# MIXR_Processing_-_STM32_DSP_Misc.net
KiCad netlist of a schematic drawn in Altium Designer
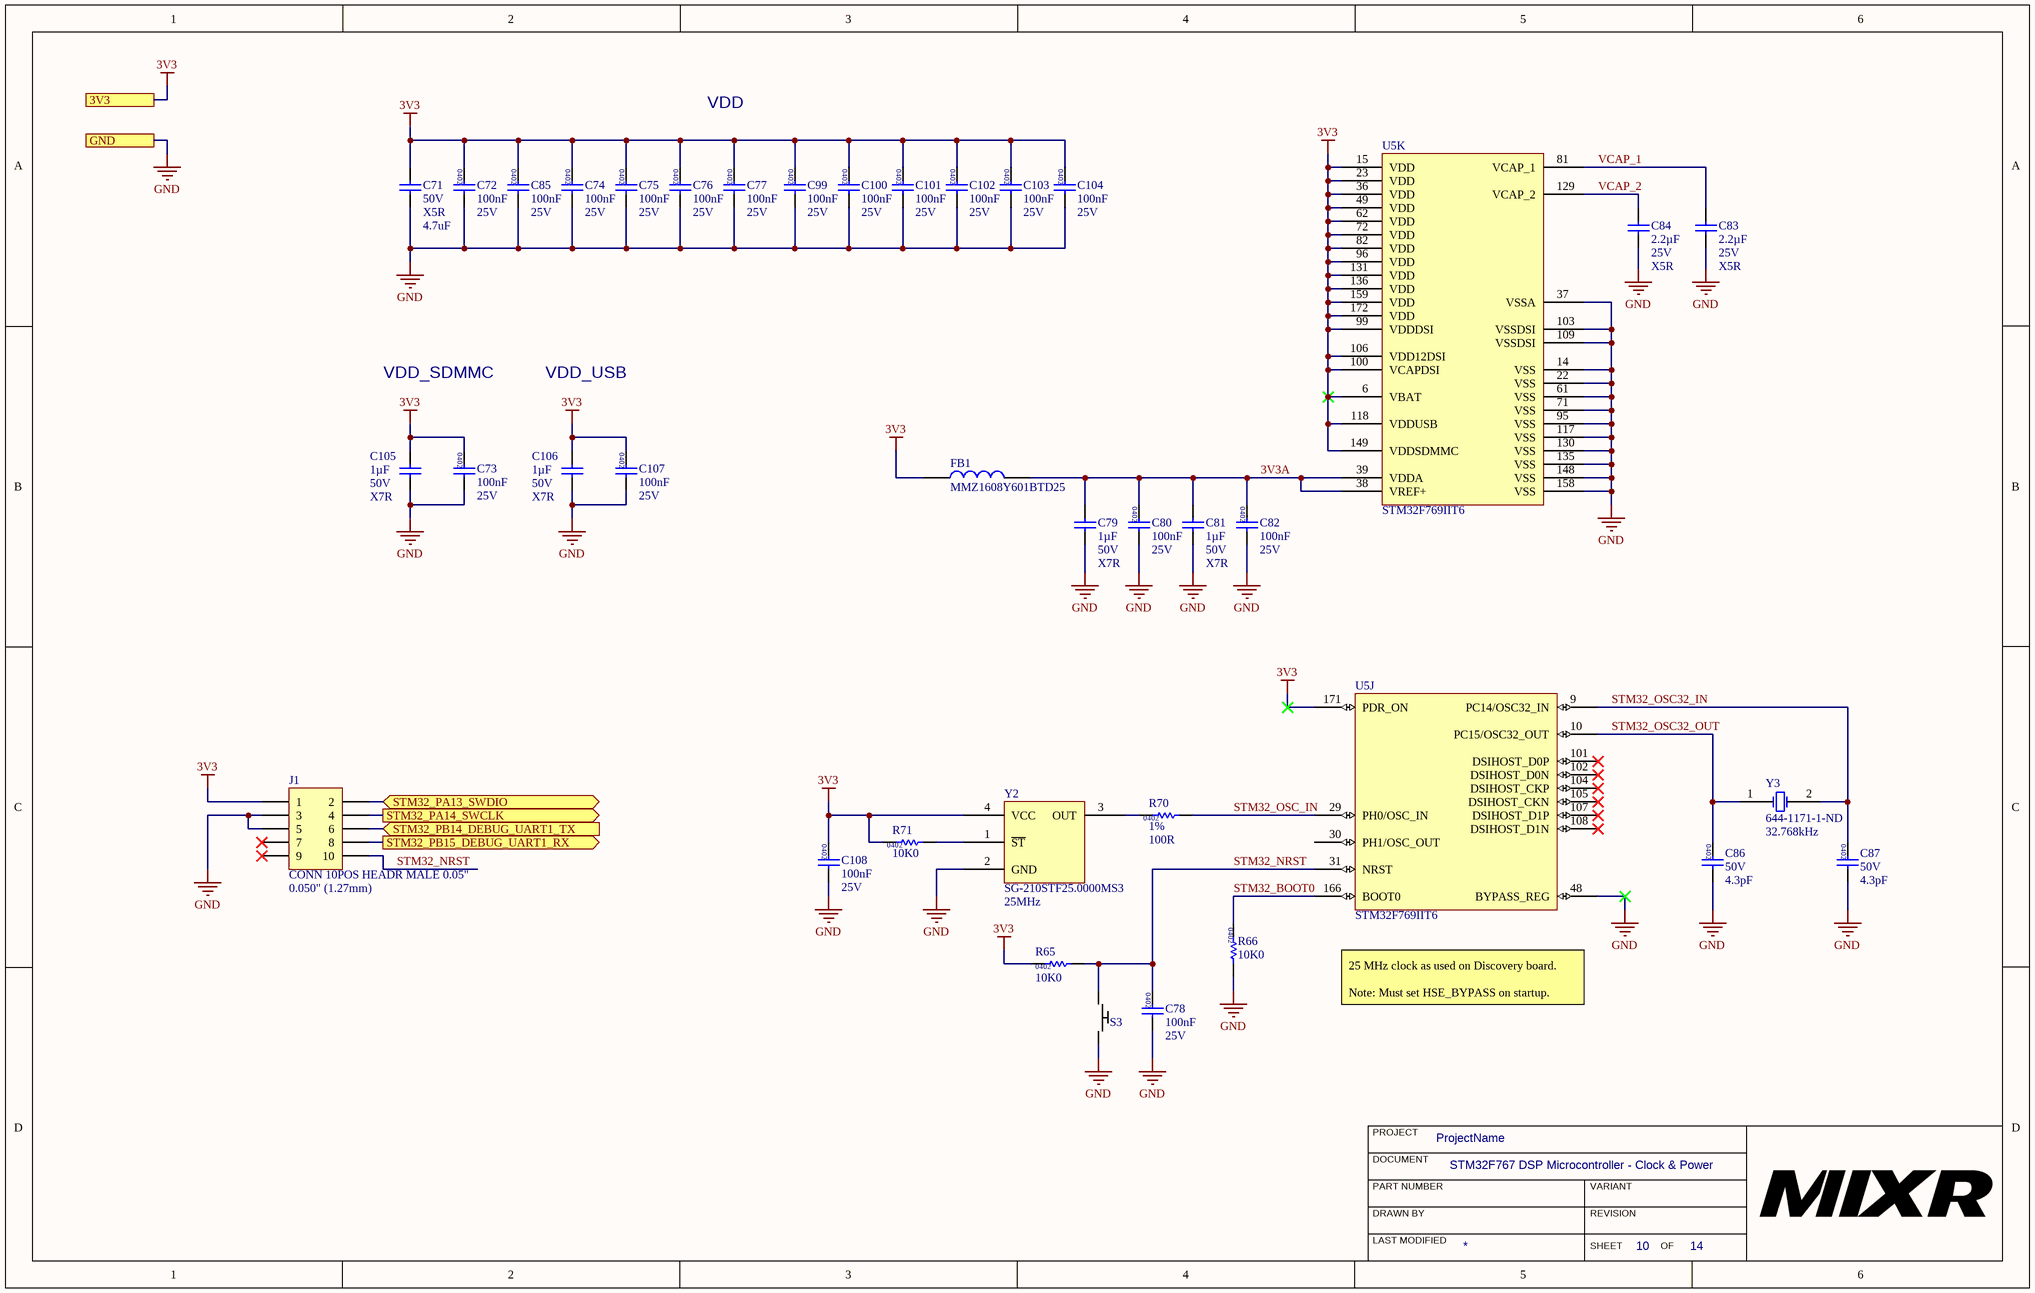
[diagram p0: MIXR Processing - STM32 DSP Misc.SchDoc]

(export (version "E")
  (design (tool "Eeschema 10.0.6"))
  (components
    (comp (ref "C71")
      (value "4.7uF")
      (footprint "CAP, 0805")
      (description "4.7µF ±20% 50V Ceramic Capacitor X5R 0805 (2012 Metric)")
      (fields
        (field (name "TOLERANCE") "±20%")
        (field (name "VOLTAGE - RATED") "50V")
        (field (name "TEMPERATURE COEFFICIENT") "X5R")
        (field (name "Comment") "CAP CER 4.7UF 50V 10% X5R 0805")
      )
      (libsource (lib "Schematic Diagrams") (part "CAP CER 4.7UF 50V 10% X5R 0805"))
    )
    (comp (ref "C72")
      (value "CAP CER 0.1UF 16V X7R 0402")
      (footprint "CAP 0402")
      (description "Cap Ceramic 0.1uF 25V X7R 10% SMD 0402 125C Paper T/R")
      (fields
        (field (name "TOLERANCE") "10%")
        (field (name "CAPACITANCE") "100nF")
        (field (name "VOLTAGE") "25V")
        (field (name "MANUFACTURER") "Murata")
      )
      (libsource (lib "Schematic Diagrams") (part "CAP CER 0.1UF 16V X7R 0402"))
    )
    (comp (ref "C73")
      (value "CAP CER 0.1UF 16V X7R 0402")
      (footprint "CAP 0402")
      (description "Cap Ceramic 0.1uF 25V X7R 10% SMD 0402 125C Paper T/R")
      (fields
        (field (name "TOLERANCE") "10%")
        (field (name "CAPACITANCE") "100nF")
        (field (name "VOLTAGE") "25V")
        (field (name "MANUFACTURER") "Murata")
      )
      (libsource (lib "Schematic Diagrams") (part "CAP CER 0.1UF 16V X7R 0402"))
    )
    (comp (ref "C74")
      (value "CAP CER 0.1UF 16V X7R 0402")
      (footprint "CAP 0402")
      (description "Cap Ceramic 0.1uF 25V X7R 10% SMD 0402 125C Paper T/R")
      (fields
        (field (name "TOLERANCE") "10%")
        (field (name "CAPACITANCE") "100nF")
        (field (name "VOLTAGE") "25V")
        (field (name "MANUFACTURER") "Murata")
      )
      (libsource (lib "Schematic Diagrams") (part "CAP CER 0.1UF 16V X7R 0402"))
    )
    (comp (ref "C75")
      (value "CAP CER 0.1UF 16V X7R 0402")
      (footprint "CAP 0402")
      (description "Cap Ceramic 0.1uF 25V X7R 10% SMD 0402 125C Paper T/R")
      (fields
        (field (name "TOLERANCE") "10%")
        (field (name "CAPACITANCE") "100nF")
        (field (name "VOLTAGE") "25V")
        (field (name "MANUFACTURER") "Murata")
      )
      (libsource (lib "Schematic Diagrams") (part "CAP CER 0.1UF 16V X7R 0402"))
    )
    (comp (ref "C76")
      (value "CAP CER 0.1UF 16V X7R 0402")
      (footprint "CAP 0402")
      (description "Cap Ceramic 0.1uF 25V X7R 10% SMD 0402 125C Paper T/R")
      (fields
        (field (name "TOLERANCE") "10%")
        (field (name "CAPACITANCE") "100nF")
        (field (name "VOLTAGE") "25V")
        (field (name "MANUFACTURER") "Murata")
      )
      (libsource (lib "Schematic Diagrams") (part "CAP CER 0.1UF 16V X7R 0402"))
    )
    (comp (ref "C77")
      (value "CAP CER 0.1UF 16V X7R 0402")
      (footprint "CAP 0402")
      (description "Cap Ceramic 0.1uF 25V X7R 10% SMD 0402 125C Paper T/R")
      (fields
        (field (name "TOLERANCE") "10%")
        (field (name "CAPACITANCE") "100nF")
        (field (name "VOLTAGE") "25V")
        (field (name "MANUFACTURER") "Murata")
      )
      (libsource (lib "Schematic Diagrams") (part "CAP CER 0.1UF 16V X7R 0402"))
    )
    (comp (ref "C78")
      (value "CAP CER 0.1UF 16V X7R 0402")
      (footprint "CAP 0402")
      (description "Cap Ceramic 0.1uF 25V X7R 10% SMD 0402 125C Paper T/R")
      (fields
        (field (name "TOLERANCE") "10%")
        (field (name "CAPACITANCE") "100nF")
        (field (name "VOLTAGE") "25V")
        (field (name "MANUFACTURER") "Murata")
      )
      (libsource (lib "Schematic Diagrams") (part "CAP CER 0.1UF 16V X7R 0402"))
    )
    (comp (ref "C79")
      (value "CAP CER 1UF 50V 10% X7R 0603")
      (footprint "CAP, 0603")
      (description "1µF ±10% 50V Ceramic Capacitor X7R 0603 (1608 Metric)")
      (fields
        (field (name "TOLERANCE") "±10%")
        (field (name "CAPACITANCE") "1µF")
        (field (name "VOLTAGE") "50V")
        (field (name "TEMPERATURE COEFFICIENT") "X7R")
      )
      (libsource (lib "Schematic Diagrams") (part "CAP CER 1UF 50V 10% X7R 0603"))
    )
    (comp (ref "C80")
      (value "CAP CER 0.1UF 16V X7R 0402")
      (footprint "CAP 0402")
      (description "Cap Ceramic 0.1uF 25V X7R 10% SMD 0402 125C Paper T/R")
      (fields
        (field (name "TOLERANCE") "10%")
        (field (name "CAPACITANCE") "100nF")
        (field (name "VOLTAGE") "25V")
        (field (name "MANUFACTURER") "Murata")
      )
      (libsource (lib "Schematic Diagrams") (part "CAP CER 0.1UF 16V X7R 0402"))
    )
    (comp (ref "C81")
      (value "CAP CER 1UF 50V 10% X7R 0603")
      (footprint "CAP, 0603")
      (description "1µF ±10% 50V Ceramic Capacitor X7R 0603 (1608 Metric)")
      (fields
        (field (name "TOLERANCE") "±10%")
        (field (name "CAPACITANCE") "1µF")
        (field (name "VOLTAGE") "50V")
        (field (name "TEMPERATURE COEFFICIENT") "X7R")
      )
      (libsource (lib "Schematic Diagrams") (part "CAP CER 1UF 50V 10% X7R 0603"))
    )
    (comp (ref "C82")
      (value "CAP CER 0.1UF 16V X7R 0402")
      (footprint "CAP 0402")
      (description "Cap Ceramic 0.1uF 25V X7R 10% SMD 0402 125C Paper T/R")
      (fields
        (field (name "TOLERANCE") "10%")
        (field (name "CAPACITANCE") "100nF")
        (field (name "VOLTAGE") "25V")
        (field (name "MANUFACTURER") "Murata")
      )
      (libsource (lib "Schematic Diagrams") (part "CAP CER 0.1UF 16V X7R 0402"))
    )
    (comp (ref "C83")
      (value "CAP CER 2.2UF 25V 10% X5R 0603")
      (footprint "CAP, 0603")
      (description "2.2µF ±10% 25V Ceramic Capacitor X5R 0603 (1608 Metric)")
      (fields
        (field (name "TOLERANCE") "±10%")
        (field (name "CAPACITANCE") "2.2µF")
        (field (name "VOLTAGE") "25V")
        (field (name "TEMPERATURE COEFFICIENT") "X5R")
      )
      (libsource (lib "Schematic Diagrams") (part "CAP CER 2.2UF 25V 10% X5R 0603"))
    )
    (comp (ref "C84")
      (value "CAP CER 2.2UF 25V 10% X5R 0603")
      (footprint "CAP, 0603")
      (description "2.2µF ±10% 25V Ceramic Capacitor X5R 0603 (1608 Metric)")
      (fields
        (field (name "TOLERANCE") "±10%")
        (field (name "CAPACITANCE") "2.2µF")
        (field (name "VOLTAGE") "25V")
        (field (name "TEMPERATURE COEFFICIENT") "X5R")
      )
      (libsource (lib "Schematic Diagrams") (part "CAP CER 2.2UF 25V 10% X5R 0603"))
    )
    (comp (ref "C85")
      (value "CAP CER 0.1UF 16V X7R 0402")
      (footprint "CAP 0402")
      (description "Cap Ceramic 0.1uF 25V X7R 10% SMD 0402 125C Paper T/R")
      (fields
        (field (name "TOLERANCE") "10%")
        (field (name "CAPACITANCE") "100nF")
        (field (name "VOLTAGE") "25V")
        (field (name "MANUFACTURER") "Murata")
      )
      (libsource (lib "Schematic Diagrams") (part "CAP CER 0.1UF 16V X7R 0402"))
    )
    (comp (ref "C86")
      (value "CAP CER 4.3PF 50V C0G/NPO 0402")
      (footprint "CAP 0402")
      (description "Multilayer Ceramic Capacitors MLCC - SMD/SMT 0402 4.3pF 50Volts C0G +/-0.1pF")
      (fields
        (field (name "MANUFACTURER") "Murata")
        (field (name "MANUFACTURER PART NUMBER") "GJM1555C1H4R3BB01D")
        (field (name "VOLTAGE RATING") "50V")
        (field (name "CAPACITANCE") "4.3pF")
      )
      (libsource (lib "Schematic Diagrams") (part "CAP CER 4.3PF 50V C0G/NPO 0402"))
    )
    (comp (ref "C87")
      (value "CAP CER 4.3PF 50V C0G/NPO 0402")
      (footprint "CAP 0402")
      (description "Multilayer Ceramic Capacitors MLCC - SMD/SMT 0402 4.3pF 50Volts C0G +/-0.1pF")
      (fields
        (field (name "MANUFACTURER") "Murata")
        (field (name "MANUFACTURER PART NUMBER") "GJM1555C1H4R3BB01D")
        (field (name "VOLTAGE RATING") "50V")
        (field (name "CAPACITANCE") "4.3pF")
      )
      (libsource (lib "Schematic Diagrams") (part "CAP CER 4.3PF 50V C0G/NPO 0402"))
    )
    (comp (ref "C99")
      (value "CAP CER 0.1UF 16V X7R 0402")
      (footprint "CAP 0402")
      (description "Cap Ceramic 0.1uF 25V X7R 10% SMD 0402 125C Paper T/R")
      (fields
        (field (name "TOLERANCE") "10%")
        (field (name "CAPACITANCE") "100nF")
        (field (name "VOLTAGE") "25V")
        (field (name "MANUFACTURER") "Murata")
      )
      (libsource (lib "Schematic Diagrams") (part "CAP CER 0.1UF 16V X7R 0402"))
    )
    (comp (ref "C100")
      (value "CAP CER 0.1UF 16V X7R 0402")
      (footprint "CAP 0402")
      (description "Cap Ceramic 0.1uF 25V X7R 10% SMD 0402 125C Paper T/R")
      (fields
        (field (name "TOLERANCE") "10%")
        (field (name "CAPACITANCE") "100nF")
        (field (name "VOLTAGE") "25V")
        (field (name "MANUFACTURER") "Murata")
      )
      (libsource (lib "Schematic Diagrams") (part "CAP CER 0.1UF 16V X7R 0402"))
    )
    (comp (ref "C101")
      (value "CAP CER 0.1UF 16V X7R 0402")
      (footprint "CAP 0402")
      (description "Cap Ceramic 0.1uF 25V X7R 10% SMD 0402 125C Paper T/R")
      (fields
        (field (name "TOLERANCE") "10%")
        (field (name "CAPACITANCE") "100nF")
        (field (name "VOLTAGE") "25V")
        (field (name "MANUFACTURER") "Murata")
      )
      (libsource (lib "Schematic Diagrams") (part "CAP CER 0.1UF 16V X7R 0402"))
    )
    (comp (ref "C102")
      (value "CAP CER 0.1UF 16V X7R 0402")
      (footprint "CAP 0402")
      (description "Cap Ceramic 0.1uF 25V X7R 10% SMD 0402 125C Paper T/R")
      (fields
        (field (name "TOLERANCE") "10%")
        (field (name "CAPACITANCE") "100nF")
        (field (name "VOLTAGE") "25V")
        (field (name "MANUFACTURER") "Murata")
      )
      (libsource (lib "Schematic Diagrams") (part "CAP CER 0.1UF 16V X7R 0402"))
    )
    (comp (ref "C103")
      (value "CAP CER 0.1UF 16V X7R 0402")
      (footprint "CAP 0402")
      (description "Cap Ceramic 0.1uF 25V X7R 10% SMD 0402 125C Paper T/R")
      (fields
        (field (name "TOLERANCE") "10%")
        (field (name "CAPACITANCE") "100nF")
        (field (name "VOLTAGE") "25V")
        (field (name "MANUFACTURER") "Murata")
      )
      (libsource (lib "Schematic Diagrams") (part "CAP CER 0.1UF 16V X7R 0402"))
    )
    (comp (ref "C104")
      (value "CAP CER 0.1UF 16V X7R 0402")
      (footprint "CAP 0402")
      (description "Cap Ceramic 0.1uF 25V X7R 10% SMD 0402 125C Paper T/R")
      (fields
        (field (name "TOLERANCE") "10%")
        (field (name "CAPACITANCE") "100nF")
        (field (name "VOLTAGE") "25V")
        (field (name "MANUFACTURER") "Murata")
      )
      (libsource (lib "Schematic Diagrams") (part "CAP CER 0.1UF 16V X7R 0402"))
    )
    (comp (ref "C105")
      (value "CAP CER 1UF 50V 10% X7R 0603")
      (footprint "CAP, 0603")
      (description "1µF ±10% 50V Ceramic Capacitor X7R 0603 (1608 Metric)")
      (fields
        (field (name "TOLERANCE") "±10%")
        (field (name "CAPACITANCE") "1µF")
        (field (name "VOLTAGE") "50V")
        (field (name "TEMPERATURE COEFFICIENT") "X7R")
      )
      (libsource (lib "Schematic Diagrams") (part "CAP CER 1UF 50V 10% X7R 0603"))
    )
    (comp (ref "C106")
      (value "CAP CER 1UF 50V 10% X7R 0603")
      (footprint "CAP, 0603")
      (description "1µF ±10% 50V Ceramic Capacitor X7R 0603 (1608 Metric)")
      (fields
        (field (name "TOLERANCE") "±10%")
        (field (name "CAPACITANCE") "1µF")
        (field (name "VOLTAGE") "50V")
        (field (name "TEMPERATURE COEFFICIENT") "X7R")
      )
      (libsource (lib "Schematic Diagrams") (part "CAP CER 1UF 50V 10% X7R 0603"))
    )
    (comp (ref "C107")
      (value "CAP CER 0.1UF 16V X7R 0402")
      (footprint "CAP 0402")
      (description "Cap Ceramic 0.1uF 25V X7R 10% SMD 0402 125C Paper T/R")
      (fields
        (field (name "TOLERANCE") "10%")
        (field (name "CAPACITANCE") "100nF")
        (field (name "VOLTAGE") "25V")
        (field (name "MANUFACTURER") "Murata")
      )
      (libsource (lib "Schematic Diagrams") (part "CAP CER 0.1UF 16V X7R 0402"))
    )
    (comp (ref "C108")
      (value "CAP CER 0.1UF 16V X7R 0402")
      (footprint "CAP 0402")
      (description "Cap Ceramic 0.1uF 25V X7R 10% SMD 0402 125C Paper T/R")
      (fields
        (field (name "TOLERANCE") "10%")
        (field (name "CAPACITANCE") "100nF")
        (field (name "VOLTAGE") "25V")
        (field (name "MANUFACTURER") "Murata")
      )
      (libsource (lib "Schematic Diagrams") (part "CAP CER 0.1UF 16V X7R 0402"))
    )
    (comp (ref "FB1")
      (value "FB 600 OHM 1LN 0603")
      (footprint "FB 0603")
      (description "FERRITE BEAD 600 OHM 0603 1LN")
      (fields
        (field (name "MANUFACTURER") "TDK")
        (field (name "TOLERANCE") "25%")
        (field (name "MANUFACTURER PART NUMBER") "MMZ1608Y601BTD25")
      )
      (libsource (lib "Schematic Diagrams") (part "FB 600 OHM 1LN 0603"))
    )
    (comp (ref "J1")
      (value "CONN 10POS HEADR MALE 0.05\"")
      (footprint "CONN, 10POS 0.05\" Debug Header")
      (description "10 Positions Header Connector 0.050\" (1.27mm) Surface Mount Gold")
      (fields (field (name "PITCH - MATING") "0.050\" (1.27mm)"))
      (libsource (lib "Schematic Diagrams") (part "CONN 10POS HEADR MALE 0.05{dblquote}"))
    )
    (comp (ref "R65")
      (value "RES 10K OHM 1% 1/16W 0402")
      (footprint "RES 0402")
      (description "Surface Mount Thick Film Resistor, Rc Series, 10 Kohm, 62.5 Mw, - 1%, 50 V, 0402 [1005 Metric]")
      (fields
        (field (name "TOLERANCE") "1%")
        (field (name "RESISTANCE") "10K0")
        (field (name "MANUFACTURER") "Yageo")
      )
      (libsource (lib "Schematic Diagrams") (part "RES 10K OHM 1% 1/16W 0402"))
    )
    (comp (ref "R66")
      (value "RES 10K OHM 1% 1/16W 0402")
      (footprint "RES 0402")
      (description "Surface Mount Thick Film Resistor, Rc Series, 10 Kohm, 62.5 Mw, - 1%, 50 V, 0402 [1005 Metric]")
      (fields
        (field (name "TOLERANCE") "1%")
        (field (name "RESISTANCE") "10K0")
        (field (name "MANUFACTURER") "Yageo")
      )
      (libsource (lib "Schematic Diagrams") (part "RES 10K OHM 1% 1/16W 0402"))
    )
    (comp (ref "R70")
      (value "RES 100 OHM 1% 1/16W 0402")
      (footprint "RES 0402")
      (description "100 Ohms ±1% 0.063W, 1/16W Chip Resistor 0402 (1005 Metric) Moisture Resistant Thick Film")
      (fields
        (field (name "MANUFACTURER") "Yageo")
        (field (name "MANUFACTURER PART NUMBER") "RC0402FR-07100RL")
        (field (name "TOLERANCE") "1%")
        (field (name "RESISTANCE") "100R")
      )
      (libsource (lib "Schematic Diagrams") (part "RES 100 OHM 1% 1/16W 0402"))
    )
    (comp (ref "R71")
      (value "RES 10K OHM 1% 1/16W 0402")
      (footprint "RES 0402")
      (description "Surface Mount Thick Film Resistor, Rc Series, 10 Kohm, 62.5 Mw, - 1%, 50 V, 0402 [1005 Metric]")
      (fields
        (field (name "TOLERANCE") "1%")
        (field (name "RESISTANCE") "10K0")
        (field (name "MANUFACTURER") "Yageo")
      )
      (libsource (lib "Schematic Diagrams") (part "RES 10K OHM 1% 1/16W 0402"))
    )
    (comp (ref "S3")
      (value "SPST")
      (footprint "SW SPST-NO 0.05A 12V")
      (description "SWITCH TACTILE SPST-NO 50MA 12V")
      (fields
        (field (name "MANUFACTURER") "E-Switch")
        (field (name "MANUFACTURER PART NUMBER") "TL3305AF260QG")
      )
      (libsource (lib "Schematic Diagrams") (part "SW SPST-NO 0.05A 12V"))
    )
    (comp (ref "U5")
      (value "IC MCU STM32F769II 176-LQFP")
      (footprint "TSQFP50P2600X2600X160-176M")
      (description "ARM® Cortex®-M7 STM32F7 Microcontroller IC 32-Bit 216MHz 2MB (2M x 8) FLASH 176-LQFP (24x24)")
      (fields
        (field (name "MANUFACTURER") "STMicroelectronics")
        (field (name "MANUFACTURER PART NUMBER") "STM32F769IIT6")
      )
      (libsource (lib "Schematic Diagrams") (part "IC MCU STM32F769II 176-LQFP"))
    )
    (comp (ref "Y2")
      (value "CRYSTAL 25 MHz OSC XO CMOS SMD")
      (footprint "CRYSTAL 25 MHz OSC XO CMOS SMD")
      (description "XTAL OSC XO 25.0000MHZ CMOS SMD")
      (fields
        (field (name "MANUFACTURER") "Epson")
        (field (name "MANUFACTURER PART NUMBER") "SG-210STF25.0000MS3")
        (field (name "FREQUENCY") "25MHz")
      )
      (libsource (lib "Schematic Diagrams") (part "CRYSTAL 25 MHz OSC XO CMOS SMD"))
    )
    (comp (ref "Y3")
      (value "CRYSTAL 32.7680 KHZ 6PF 2-SMD")
      (footprint "CRYSTAL 32.7680 KHZ 6PF 2-SMD")
      (description "Crystal 32.7680KHZ 6PF SMD")
      (fields
        (field (name "MANUFACTURER") "NDK")
        (field (name "MANUFACTURER PART NUMBER") "NX3215SA-32.768K-STD-MUA-14")
        (field (name "SUPPLIER PART NUMBER 1") "644-1171-1-ND")
        (field (name "FREQUENCY") "32.768kHz")
      )
      (libsource (lib "Schematic Diagrams") (part "CRYSTAL 32.7680 KHZ 6PF 2-SMD"))
    )
  )
  (nets
    (net (code "1") (name "/3V3A") (class "Default")
      (node (ref "C79") (pin "1") (pinfunction "1_1") (pintype "passive"))
      (node (ref "C80") (pin "1") (pinfunction "1_1") (pintype "passive"))
      (node (ref "C81") (pin "1") (pinfunction "1_1") (pintype "passive"))
      (node (ref "C82") (pin "1") (pinfunction "1_1") (pintype "passive"))
      (node (ref "FB1") (pin "2") (pinfunction "2_2") (pintype "passive"))
      (node (ref "U5") (pin "38") (pinfunction "VREF+_38") (pintype "power_in"))
      (node (ref "U5") (pin "39") (pinfunction "VDDA_39") (pintype "power_in"))
    )
    (net (code "2") (name "/STM32_BOOT0") (class "Default")
      (node (ref "R66") (pin "1") (pinfunction "1_1") (pintype "passive"))
      (node (ref "U5") (pin "166") (pinfunction "BOOT0_166") (pintype "bidirectional"))
    )
    (net (code "3") (name "/STM32_NRST") (class "Default")
      (node (ref "C78") (pin "1") (pinfunction "1_1") (pintype "passive"))
      (node (ref "J1") (pin "10") (pinfunction "10_10") (pintype "passive"))
      (node (ref "R65") (pin "2") (pinfunction "2_2") (pintype "passive"))
      (node (ref "S3") (pin "1") (pinfunction "1_1") (pintype "passive"))
      (node (ref "U5") (pin "31") (pinfunction "NRST_31") (pintype "bidirectional"))
    )
    (net (code "4") (name "/STM32_OSC32_IN") (class "Default")
      (node (ref "C87") (pin "1") (pinfunction "1_1") (pintype "passive"))
      (node (ref "U5") (pin "9") (pinfunction "PC14/OSC32_IN_9") (pintype "bidirectional"))
      (node (ref "Y3") (pin "2") (pinfunction "2_2") (pintype "passive"))
    )
    (net (code "5") (name "/STM32_OSC32_OUT") (class "Default")
      (node (ref "C86") (pin "1") (pinfunction "1_1") (pintype "passive"))
      (node (ref "U5") (pin "10") (pinfunction "PC15/OSC32_OUT_10") (pintype "bidirectional"))
      (node (ref "Y3") (pin "1") (pinfunction "1_1") (pintype "passive"))
    )
    (net (code "6") (name "/STM32_OSC_IN") (class "Default")
      (node (ref "R70") (pin "2") (pinfunction "2_2") (pintype "passive"))
      (node (ref "U5") (pin "29") (pinfunction "PH0/OSC_IN_29") (pintype "bidirectional"))
    )
    (net (code "7") (name "/STM32_PA13_SWDIO") (class "Default")
      (node (ref "J1") (pin "2") (pinfunction "2_2") (pintype "passive"))
    )
    (net (code "8") (name "/STM32_PA14_SWCLK") (class "Default")
      (node (ref "J1") (pin "4") (pinfunction "4_4") (pintype "passive"))
    )
    (net (code "9") (name "/STM32_PB14_DEBUG_UART1_TX") (class "Default")
      (node (ref "J1") (pin "6") (pinfunction "6_6") (pintype "passive"))
    )
    (net (code "10") (name "/STM32_PB15_DEBUG_UART1_RX") (class "Default")
      (node (ref "J1") (pin "8") (pinfunction "8_8") (pintype "passive"))
    )
    (net (code "11") (name "/VCAP_1") (class "Default")
      (node (ref "C83") (pin "1") (pinfunction "1_1") (pintype "passive"))
      (node (ref "U5") (pin "81") (pinfunction "VCAP_1_81") (pintype "power_in"))
    )
    (net (code "12") (name "/VCAP_2") (class "Default")
      (node (ref "C84") (pin "1") (pinfunction "1_1") (pintype "passive"))
      (node (ref "U5") (pin "129") (pinfunction "VCAP_2_129") (pintype "power_in"))
    )
    (net (code "13") (name "3V3") (class "Default")
      (node (ref "C100") (pin "1") (pinfunction "1_1") (pintype "passive"))
      (node (ref "C101") (pin "1") (pinfunction "1_1") (pintype "passive"))
      (node (ref "C102") (pin "1") (pinfunction "1_1") (pintype "passive"))
      (node (ref "C103") (pin "1") (pinfunction "1_1") (pintype "passive"))
      (node (ref "C104") (pin "1") (pinfunction "1_1") (pintype "passive"))
      (node (ref "C105") (pin "1") (pinfunction "1_1") (pintype "passive"))
      (node (ref "C106") (pin "1") (pinfunction "1_1") (pintype "passive"))
      (node (ref "C107") (pin "1") (pinfunction "1_1") (pintype "passive"))
      (node (ref "C108") (pin "1") (pinfunction "1_1") (pintype "passive"))
      (node (ref "C71") (pin "1") (pinfunction "1_1") (pintype "passive"))
      (node (ref "C72") (pin "1") (pinfunction "1_1") (pintype "passive"))
      (node (ref "C73") (pin "1") (pinfunction "1_1") (pintype "passive"))
      (node (ref "C74") (pin "1") (pinfunction "1_1") (pintype "passive"))
      (node (ref "C75") (pin "1") (pinfunction "1_1") (pintype "passive"))
      (node (ref "C76") (pin "1") (pinfunction "1_1") (pintype "passive"))
      (node (ref "C77") (pin "1") (pinfunction "1_1") (pintype "passive"))
      (node (ref "C85") (pin "1") (pinfunction "1_1") (pintype "passive"))
      (node (ref "C99") (pin "1") (pinfunction "1_1") (pintype "passive"))
      (node (ref "FB1") (pin "1") (pinfunction "1_1") (pintype "passive"))
      (node (ref "J1") (pin "1") (pinfunction "1_1") (pintype "passive"))
      (node (ref "R65") (pin "1") (pinfunction "1_1") (pintype "passive"))
      (node (ref "R71") (pin "1") (pinfunction "1_1") (pintype "passive"))
      (node (ref "U5") (pin "100") (pinfunction "VCAPDSI_100") (pintype "power_in"))
      (node (ref "U5") (pin "106") (pinfunction "VDD12DSI_106") (pintype "power_in"))
      (node (ref "U5") (pin "118") (pinfunction "VDDUSB_118") (pintype "power_in"))
      (node (ref "U5") (pin "131") (pinfunction "VDD_131") (pintype "power_in"))
      (node (ref "U5") (pin "136") (pinfunction "VDD_136") (pintype "power_in"))
      (node (ref "U5") (pin "149") (pinfunction "VDDSDMMC_149") (pintype "power_in"))
      (node (ref "U5") (pin "15") (pinfunction "VDD_15") (pintype "power_in"))
      (node (ref "U5") (pin "159") (pinfunction "VDD_159") (pintype "power_in"))
      (node (ref "U5") (pin "171") (pinfunction "PDR_ON_171") (pintype "bidirectional"))
      (node (ref "U5") (pin "172") (pinfunction "VDD_172") (pintype "power_in"))
      (node (ref "U5") (pin "23") (pinfunction "VDD_23") (pintype "power_in"))
      (node (ref "U5") (pin "36") (pinfunction "VDD_36") (pintype "power_in"))
      (node (ref "U5") (pin "49") (pinfunction "VDD_49") (pintype "power_in"))
      (node (ref "U5") (pin "6") (pinfunction "VBAT_6") (pintype "power_in"))
      (node (ref "U5") (pin "62") (pinfunction "VDD_62") (pintype "power_in"))
      (node (ref "U5") (pin "72") (pinfunction "VDD_72") (pintype "power_in"))
      (node (ref "U5") (pin "82") (pinfunction "VDD_82") (pintype "power_in"))
      (node (ref "U5") (pin "96") (pinfunction "VDD_96") (pintype "power_in"))
      (node (ref "U5") (pin "99") (pinfunction "VDDDSI_99") (pintype "power_in"))
      (node (ref "Y2") (pin "4") (pinfunction "VCC_4") (pintype "passive"))
    )
    (net (code "14") (name "GND") (class "Default")
      (node (ref "C100") (pin "2") (pinfunction "2_2") (pintype "passive"))
      (node (ref "C101") (pin "2") (pinfunction "2_2") (pintype "passive"))
      (node (ref "C102") (pin "2") (pinfunction "2_2") (pintype "passive"))
      (node (ref "C103") (pin "2") (pinfunction "2_2") (pintype "passive"))
      (node (ref "C104") (pin "2") (pinfunction "2_2") (pintype "passive"))
      (node (ref "C105") (pin "2") (pinfunction "2_2") (pintype "passive"))
      (node (ref "C106") (pin "2") (pinfunction "2_2") (pintype "passive"))
      (node (ref "C107") (pin "2") (pinfunction "2_2") (pintype "passive"))
      (node (ref "C108") (pin "2") (pinfunction "2_2") (pintype "passive"))
      (node (ref "C71") (pin "2") (pinfunction "2_2") (pintype "passive"))
      (node (ref "C72") (pin "2") (pinfunction "2_2") (pintype "passive"))
      (node (ref "C73") (pin "2") (pinfunction "2_2") (pintype "passive"))
      (node (ref "C74") (pin "2") (pinfunction "2_2") (pintype "passive"))
      (node (ref "C75") (pin "2") (pinfunction "2_2") (pintype "passive"))
      (node (ref "C76") (pin "2") (pinfunction "2_2") (pintype "passive"))
      (node (ref "C77") (pin "2") (pinfunction "2_2") (pintype "passive"))
      (node (ref "C78") (pin "2") (pinfunction "2_2") (pintype "passive"))
      (node (ref "C79") (pin "2") (pinfunction "2_2") (pintype "passive"))
      (node (ref "C80") (pin "2") (pinfunction "2_2") (pintype "passive"))
      (node (ref "C81") (pin "2") (pinfunction "2_2") (pintype "passive"))
      (node (ref "C82") (pin "2") (pinfunction "2_2") (pintype "passive"))
      (node (ref "C83") (pin "2") (pinfunction "2_2") (pintype "passive"))
      (node (ref "C84") (pin "2") (pinfunction "2_2") (pintype "passive"))
      (node (ref "C85") (pin "2") (pinfunction "2_2") (pintype "passive"))
      (node (ref "C86") (pin "2") (pinfunction "2_2") (pintype "passive"))
      (node (ref "C87") (pin "2") (pinfunction "2_2") (pintype "passive"))
      (node (ref "C99") (pin "2") (pinfunction "2_2") (pintype "passive"))
      (node (ref "J1") (pin "3") (pinfunction "3_3") (pintype "passive"))
      (node (ref "J1") (pin "5") (pinfunction "5_5") (pintype "passive"))
      (node (ref "R66") (pin "2") (pinfunction "2_2") (pintype "passive"))
      (node (ref "S3") (pin "2") (pinfunction "2_2") (pintype "passive"))
      (node (ref "U5") (pin "103") (pinfunction "VSSDSI_103") (pintype "power_in"))
      (node (ref "U5") (pin "109") (pinfunction "VSSDSI_109") (pintype "power_in"))
      (node (ref "U5") (pin "117") (pinfunction "VSS_117") (pintype "power_in"))
      (node (ref "U5") (pin "130") (pinfunction "VSS_130") (pintype "power_in"))
      (node (ref "U5") (pin "135") (pinfunction "VSS_135") (pintype "power_in"))
      (node (ref "U5") (pin "14") (pinfunction "VSS_14") (pintype "power_in"))
      (node (ref "U5") (pin "148") (pinfunction "VSS_148") (pintype "power_in"))
      (node (ref "U5") (pin "158") (pinfunction "VSS_158") (pintype "power_in"))
      (node (ref "U5") (pin "22") (pinfunction "VSS_22") (pintype "power_in"))
      (node (ref "U5") (pin "37") (pinfunction "VSSA_37") (pintype "power_in"))
      (node (ref "U5") (pin "48") (pinfunction "BYPASS_REG_48") (pintype "bidirectional"))
      (node (ref "U5") (pin "61") (pinfunction "VSS_61") (pintype "power_in"))
      (node (ref "U5") (pin "71") (pinfunction "VSS_71") (pintype "power_in"))
      (node (ref "U5") (pin "95") (pinfunction "VSS_95") (pintype "power_in"))
      (node (ref "Y2") (pin "2") (pinfunction "GND_2") (pintype "passive"))
    )
    (net (code "15") (name "Net-(Y2-OUT)") (class "Default")
      (node (ref "R70") (pin "1") (pinfunction "1_1") (pintype "passive"))
      (node (ref "Y2") (pin "3") (pinfunction "OUT_3") (pintype "passive"))
    )
    (net (code "16") (name "Net-(Y2-~{ST})") (class "Default")
      (node (ref "R71") (pin "2") (pinfunction "2_2") (pintype "passive"))
      (node (ref "Y2") (pin "1") (pinfunction "~{ST}_1") (pintype "passive"))
    )
    (net (code "17") (name "unconnected-(J1-Pad7)") (class "Default")
      (node (ref "J1") (pin "7") (pinfunction "7_7") (pintype "passive+no_connect"))
    )
    (net (code "18") (name "unconnected-(J1-Pad9)") (class "Default")
      (node (ref "J1") (pin "9") (pinfunction "9_9") (pintype "passive+no_connect"))
    )
    (net (code "19") (name "unconnected-(U5J-DSIHOST_CKN-Pad105)") (class "Default")
      (node (ref "U5") (pin "105") (pinfunction "DSIHOST_CKN_105") (pintype "bidirectional+no_connect"))
    )
    (net (code "20") (name "unconnected-(U5J-DSIHOST_CKP-Pad104)") (class "Default")
      (node (ref "U5") (pin "104") (pinfunction "DSIHOST_CKP_104") (pintype "bidirectional+no_connect"))
    )
    (net (code "21") (name "unconnected-(U5J-DSIHOST_D0N-Pad102)") (class "Default")
      (node (ref "U5") (pin "102") (pinfunction "DSIHOST_D0N_102") (pintype "bidirectional+no_connect"))
    )
    (net (code "22") (name "unconnected-(U5J-DSIHOST_D0P-Pad101)") (class "Default")
      (node (ref "U5") (pin "101") (pinfunction "DSIHOST_D0P_101") (pintype "bidirectional+no_connect"))
    )
    (net (code "23") (name "unconnected-(U5J-DSIHOST_D1N-Pad108)") (class "Default")
      (node (ref "U5") (pin "108") (pinfunction "DSIHOST_D1N_108") (pintype "bidirectional+no_connect"))
    )
    (net (code "24") (name "unconnected-(U5J-DSIHOST_D1P-Pad107)") (class "Default")
      (node (ref "U5") (pin "107") (pinfunction "DSIHOST_D1P_107") (pintype "bidirectional+no_connect"))
    )
    (net (code "25") (name "unconnected-(U5J-PH1{slash}OSC_OUT-Pad30)") (class "Default")
      (node (ref "U5") (pin "30") (pinfunction "PH1/OSC_OUT_30") (pintype "bidirectional"))
    )
  )
)
